# P2.net
KiCad netlist of a schematic drawn in EAGLE
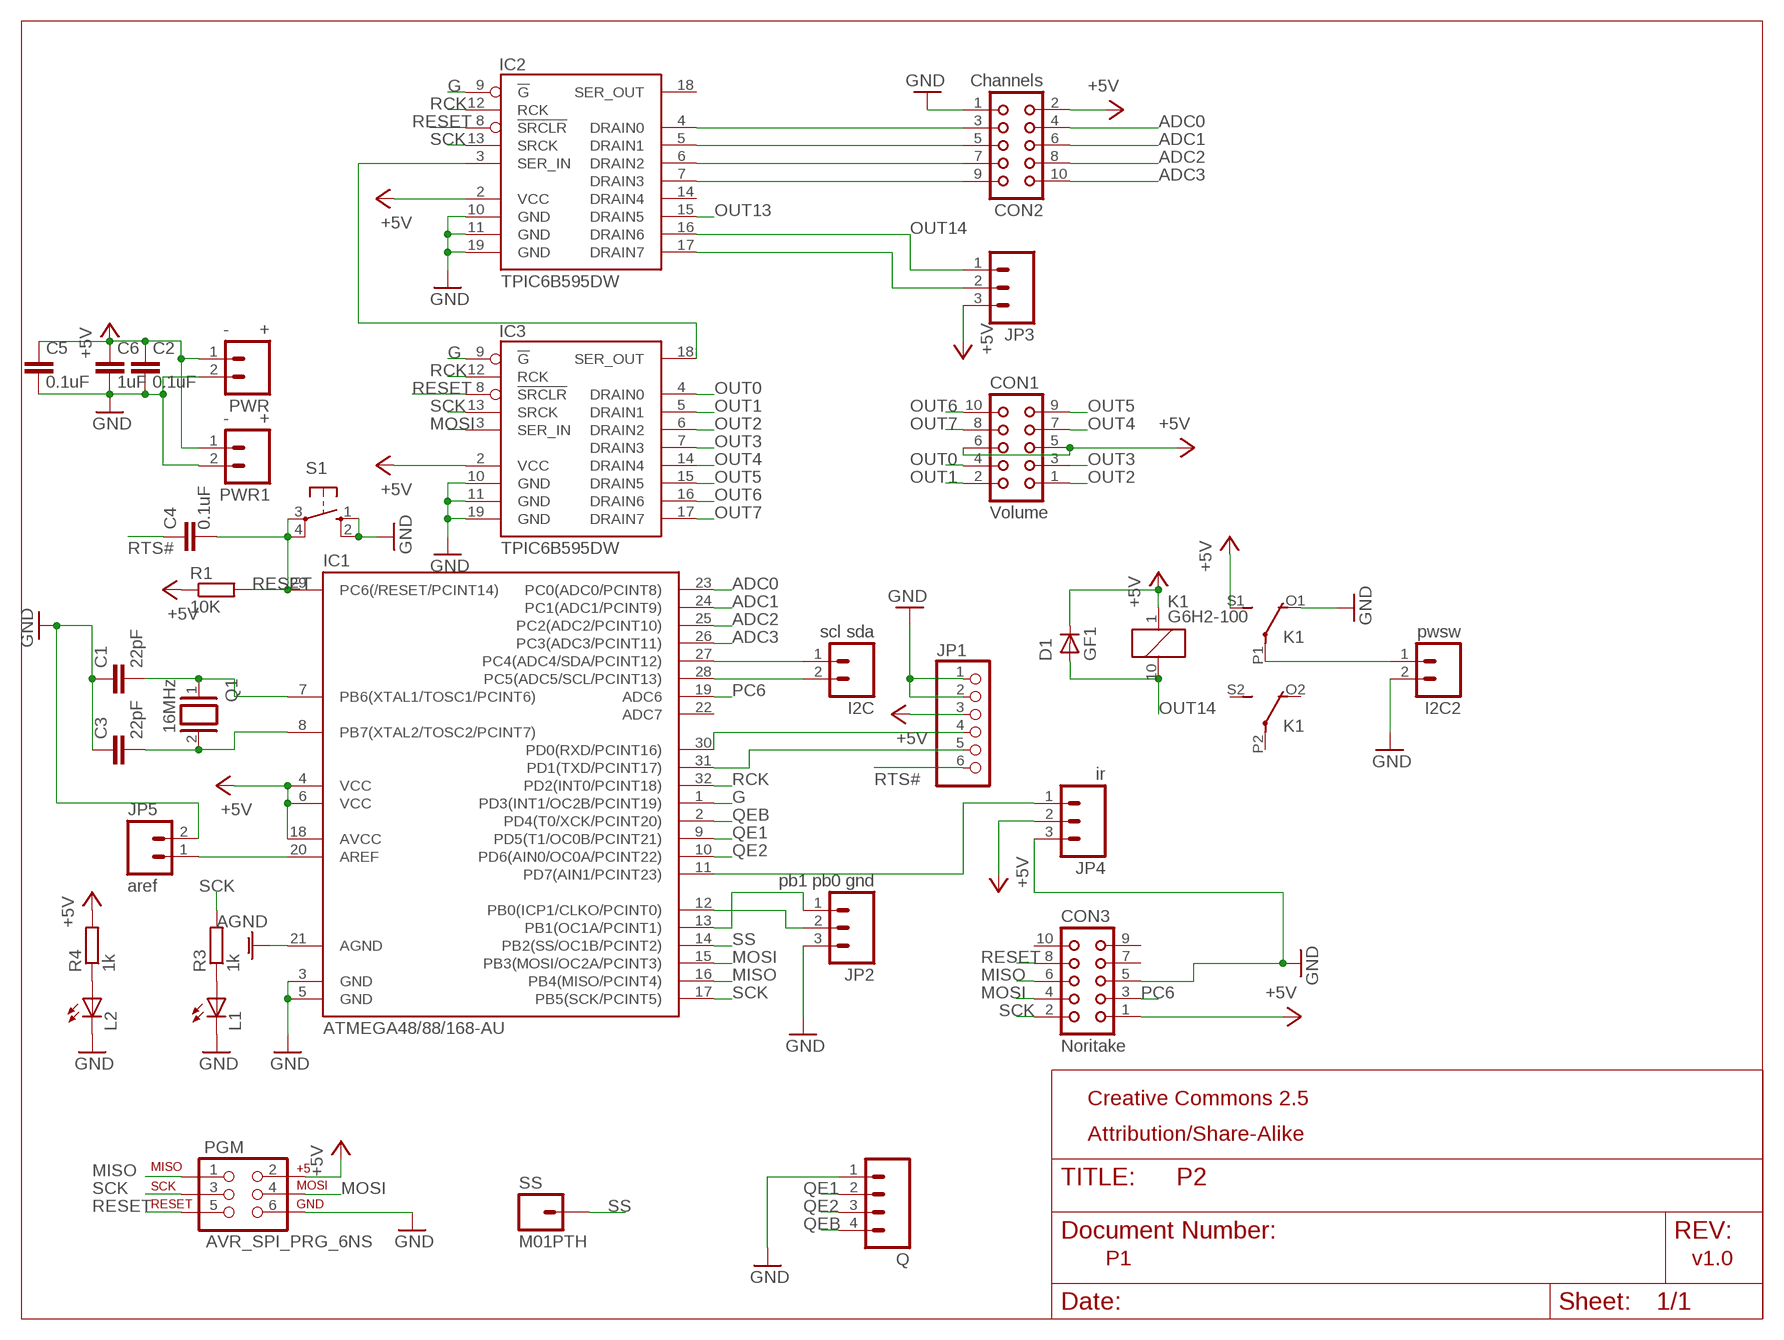
[diagram p0: schematic, sheet 1]

(export (version "E")
  (design (tool "Eeschema 10.0.6"))
  (components
    (comp (ref "C1")
      (value "22pF")
      (footprint "eagle-import:C0805")
      (libsource (lib "eagle-import") (part "C-EUC0805"))
    )
    (comp (ref "C2")
      (value "0.1uF")
      (footprint "eagle-import:C0805")
      (libsource (lib "eagle-import") (part "C-EUC0805"))
    )
    (comp (ref "C3")
      (value "22pF")
      (footprint "eagle-import:C0805")
      (libsource (lib "eagle-import") (part "C-EUC0805"))
    )
    (comp (ref "C4")
      (value "0.1uF")
      (footprint "eagle-import:C0805")
      (libsource (lib "eagle-import") (part "C-EUC0805"))
    )
    (comp (ref "C5")
      (value "0.1uF")
      (footprint "eagle-import:C0805")
      (libsource (lib "eagle-import") (part "C-EUC0805"))
    )
    (comp (ref "C6")
      (value "1uF")
      (footprint "eagle-import:C0805")
      (libsource (lib "eagle-import") (part "C-EUC0805"))
    )
    (comp (ref "CON1")
      (value "Volume")
      (footprint "eagle-import:CON10L")
      (libsource (lib "eagle-import") (part "CON10L"))
    )
    (comp (ref "CON2")
      (value "Channels")
      (footprint "eagle-import:CON10L")
      (libsource (lib "eagle-import") (part "CON10L"))
    )
    (comp (ref "CON3")
      (value "Noritake")
      (footprint "eagle-import:CON10L")
      (libsource (lib "eagle-import") (part "CON10L"))
    )
    (comp (ref "D1")
      (value "GF1")
      (footprint "eagle-import:SMA-DO214AC")
      (libsource (lib "eagle-import") (part "GF1"))
    )
    (comp (ref "I2C")
      (value "scl sda")
      (footprint "eagle-import:1X02")
      (libsource (lib "eagle-import") (part "M02PTH"))
    )
    (comp (ref "I2C2")
      (value "pwsw")
      (footprint "eagle-import:1X02")
      (libsource (lib "eagle-import") (part "M02PTH"))
    )
    (comp (ref "IC1")
      (value "ATMEGA48/88/168-AU")
      (footprint "eagle-import:TQFP32-08")
      (libsource (lib "eagle-import") (part "ATMEGA48/88/168-AU"))
    )
    (comp (ref "IC2")
      (value "TPIC6B595DW")
      (footprint "eagle-import:SO20W")
      (libsource (lib "eagle-import") (part "TPIC6B595DW"))
    )
    (comp (ref "IC3")
      (value "TPIC6B595DW")
      (footprint "eagle-import:SO20W")
      (libsource (lib "eagle-import") (part "TPIC6B595DW"))
    )
    (comp (ref "JP1")
      (value "PINHD-1X6CLEAN")
      (footprint "eagle-import:1X06-CLEAN")
      (libsource (lib "eagle-import") (part "PINHD-1X6CLEAN"))
    )
    (comp (ref "JP2")
      (value "pb1 pb0 gnd")
      (footprint "eagle-import:1X03")
      (libsource (lib "eagle-import") (part "M03PTH"))
    )
    (comp (ref "JP3")
      (value "M03PTH")
      (footprint "eagle-import:1X03")
      (libsource (lib "eagle-import") (part "M03PTH"))
    )
    (comp (ref "JP4")
      (value "ir")
      (footprint "eagle-import:1X03")
      (libsource (lib "eagle-import") (part "M03PTH"))
    )
    (comp (ref "JP5")
      (value "aref")
      (footprint "eagle-import:1X02")
      (libsource (lib "eagle-import") (part "M02PTH"))
    )
    (comp (ref "K1")
      (value "G6H2-100")
      (footprint "eagle-import:G6H2-100")
      (libsource (lib "eagle-import") (part "G6H2-100"))
    )
    (comp (ref "L1")
      (value "LEDSML0805")
      (footprint "eagle-import:SML0805")
      (libsource (lib "eagle-import") (part "LEDSML0805"))
    )
    (comp (ref "L2")
      (value "LEDSML0805")
      (footprint "eagle-import:SML0805")
      (libsource (lib "eagle-import") (part "LEDSML0805"))
    )
    (comp (ref "PGM")
      (value "AVR_SPI_PRG_6NS")
      (footprint "eagle-import:2X3-NS")
      (libsource (lib "eagle-import") (part "AVR_SPI_PRG_6NS"))
    )
    (comp (ref "PWR")
      (value "- +")
      (footprint "eagle-import:1X02")
      (libsource (lib "eagle-import") (part "M02PTH"))
    )
    (comp (ref "PWR1")
      (value "- +")
      (footprint "eagle-import:1X02")
      (libsource (lib "eagle-import") (part "M02PTH"))
    )
    (comp (ref "Q")
      (value "M04PTH")
      (footprint "eagle-import:1X04")
      (libsource (lib "eagle-import") (part "M04PTH"))
    )
    (comp (ref "Q1")
      (value "16MHz")
      (footprint "eagle-import:QS")
      (libsource (lib "eagle-import") (part "XTAL/S"))
    )
    (comp (ref "R1")
      (value "10K")
      (footprint "eagle-import:M0805")
      (libsource (lib "eagle-import") (part "R-EU_M0805"))
    )
    (comp (ref "R3")
      (value "1k")
      (footprint "eagle-import:M0805")
      (libsource (lib "eagle-import") (part "R-EU_M0805"))
    )
    (comp (ref "R4")
      (value "1k")
      (footprint "eagle-import:M0805")
      (libsource (lib "eagle-import") (part "R-EU_M0805"))
    )
    (comp (ref "S1")
      (value "10-XX")
      (footprint "eagle-import:B3F-10XX")
      (fields (field (name "MPN") "B3F-1000"))
      (libsource (lib "eagle-import") (part "10-XX"))
    )
    (comp (ref "SS")
      (value "M01PTH")
      (footprint "eagle-import:1X01")
      (libsource (lib "eagle-import") (part "M01PTH"))
    )
  )
  (nets
    (net (code "1") (name "+5V") (class "Default")
      (node (ref "C2") (pin "1") (pinfunction "1_1") (pintype "passive"))
      (node (ref "C5") (pin "1") (pinfunction "1_1") (pintype "passive"))
      (node (ref "C6") (pin "1") (pinfunction "1_1") (pintype "passive"))
      (node (ref "CON1") (pin "5") (pinfunction "5_5") (pintype "passive"))
      (node (ref "CON1") (pin "6") (pinfunction "6_6") (pintype "passive"))
      (node (ref "CON2") (pin "2") (pinfunction "2_2") (pintype "passive"))
      (node (ref "CON3") (pin "1") (pinfunction "1_1") (pintype "passive"))
      (node (ref "D1") (pin "K") (pinfunction "C_K") (pintype "passive"))
      (node (ref "IC1") (pin "18") (pinfunction "AVCC_18") (pintype "passive"))
      (node (ref "IC1") (pin "4") (pinfunction "VCC_4") (pintype "power_in"))
      (node (ref "IC1") (pin "6") (pinfunction "VCC_6") (pintype "power_in"))
      (node (ref "IC2") (pin "2") (pinfunction "VCC_2") (pintype "power_in"))
      (node (ref "IC3") (pin "2") (pinfunction "VCC_2") (pintype "power_in"))
      (node (ref "JP1") (pin "3") (pinfunction "3_3") (pintype "passive"))
      (node (ref "JP3") (pin "3") (pinfunction "3_3") (pintype "passive"))
      (node (ref "JP4") (pin "2") (pinfunction "2_2") (pintype "passive"))
      (node (ref "K1") (pin "1") (pinfunction "1_1") (pintype "passive"))
      (node (ref "K1") (pin "S1") (pinfunction "S_S1") (pintype "passive"))
      (node (ref "PGM") (pin "2") (pinfunction "2_2") (pintype "passive"))
      (node (ref "PWR") (pin "1") (pinfunction "1_1") (pintype "passive"))
      (node (ref "PWR1") (pin "1") (pinfunction "1_1") (pintype "passive"))
      (node (ref "R1") (pin "1") (pinfunction "1_1") (pintype "passive"))
      (node (ref "R4") (pin "2") (pinfunction "2_2") (pintype "passive"))
    )
    (net (code "2") (name "/ADC0") (class "Default")
      (node (ref "CON2") (pin "4") (pinfunction "4_4") (pintype "passive"))
      (node (ref "IC1") (pin "23") (pinfunction "PC0(ADC0/PCINT8)_23") (pintype "bidirectional"))
    )
    (net (code "3") (name "/ADC1") (class "Default")
      (node (ref "CON2") (pin "6") (pinfunction "6_6") (pintype "passive"))
      (node (ref "IC1") (pin "24") (pinfunction "PC1(ADC1/PCINT9)_24") (pintype "bidirectional"))
    )
    (net (code "4") (name "/ADC2") (class "Default")
      (node (ref "CON2") (pin "8") (pinfunction "8_8") (pintype "passive"))
      (node (ref "IC1") (pin "25") (pinfunction "PC2(ADC2/PCINT10)_25") (pintype "bidirectional"))
    )
    (net (code "5") (name "/ADC3") (class "Default")
      (node (ref "CON2") (pin "10") (pinfunction "10_10") (pintype "passive"))
      (node (ref "IC1") (pin "26") (pinfunction "PC3(ADC3/PCINT11)_26") (pintype "bidirectional"))
    )
    (net (code "6") (name "/G") (class "Default")
      (node (ref "IC1") (pin "1") (pinfunction "PD3(INT1/OC2B/PCINT19)_1") (pintype "bidirectional"))
      (node (ref "IC2") (pin "9") (pinfunction "~{G}_9") (pintype "input"))
      (node (ref "IC3") (pin "9") (pinfunction "~{G}_9") (pintype "input"))
    )
    (net (code "7") (name "/MISO") (class "Default")
      (node (ref "CON3") (pin "6") (pinfunction "6_6") (pintype "passive"))
      (node (ref "IC1") (pin "16") (pinfunction "PB4(MISO/PCINT4)_16") (pintype "bidirectional"))
      (node (ref "PGM") (pin "1") (pinfunction "1_1") (pintype "passive"))
    )
    (net (code "8") (name "/MOSI") (class "Default")
      (node (ref "CON3") (pin "4") (pinfunction "4_4") (pintype "passive"))
      (node (ref "IC1") (pin "15") (pinfunction "PB3(MOSI/OC2A/PCINT3)_15") (pintype "bidirectional"))
      (node (ref "IC3") (pin "3") (pinfunction "SER_IN_3") (pintype "input"))
      (node (ref "PGM") (pin "4") (pinfunction "4_4") (pintype "passive"))
    )
    (net (code "9") (name "/OUT0") (class "Default")
      (node (ref "CON1") (pin "4") (pinfunction "4_4") (pintype "passive"))
      (node (ref "IC3") (pin "4") (pinfunction "DRAIN0_4") (pintype "open_collector"))
    )
    (net (code "10") (name "/OUT1") (class "Default")
      (node (ref "CON1") (pin "2") (pinfunction "2_2") (pintype "passive"))
      (node (ref "IC3") (pin "5") (pinfunction "DRAIN1_5") (pintype "open_collector"))
    )
    (net (code "11") (name "/OUT2") (class "Default")
      (node (ref "CON1") (pin "1") (pinfunction "1_1") (pintype "passive"))
      (node (ref "IC3") (pin "6") (pinfunction "DRAIN2_6") (pintype "open_collector"))
    )
    (net (code "12") (name "/OUT3") (class "Default")
      (node (ref "CON1") (pin "3") (pinfunction "3_3") (pintype "passive"))
      (node (ref "IC3") (pin "7") (pinfunction "DRAIN3_7") (pintype "open_collector"))
    )
    (net (code "13") (name "/OUT4") (class "Default")
      (node (ref "CON1") (pin "7") (pinfunction "7_7") (pintype "passive"))
      (node (ref "IC3") (pin "14") (pinfunction "DRAIN4_14") (pintype "open_collector"))
    )
    (net (code "14") (name "/OUT5") (class "Default")
      (node (ref "CON1") (pin "9") (pinfunction "9_9") (pintype "passive"))
      (node (ref "IC3") (pin "15") (pinfunction "DRAIN5_15") (pintype "open_collector"))
    )
    (net (code "15") (name "/OUT6") (class "Default")
      (node (ref "CON1") (pin "10") (pinfunction "10_10") (pintype "passive"))
      (node (ref "IC3") (pin "16") (pinfunction "DRAIN6_16") (pintype "open_collector"))
    )
    (net (code "16") (name "/OUT7") (class "Default")
      (node (ref "CON1") (pin "8") (pinfunction "8_8") (pintype "passive"))
      (node (ref "IC3") (pin "17") (pinfunction "DRAIN7_17") (pintype "open_collector"))
    )
    (net (code "17") (name "/OUT13") (class "Default")
      (node (ref "IC2") (pin "15") (pinfunction "DRAIN5_15") (pintype "open_collector"))
    )
    (net (code "18") (name "/OUT14") (class "Default")
      (node (ref "D1") (pin "A") (pinfunction "A_A") (pintype "passive"))
      (node (ref "IC2") (pin "16") (pinfunction "DRAIN6_16") (pintype "open_collector"))
      (node (ref "JP3") (pin "1") (pinfunction "1_1") (pintype "passive"))
      (node (ref "K1") (pin "10") (pinfunction "2_10") (pintype "passive"))
    )
    (net (code "19") (name "/PC6") (class "Default")
      (node (ref "CON3") (pin "3") (pinfunction "3_3") (pintype "passive"))
      (node (ref "IC1") (pin "19") (pinfunction "ADC6_19") (pintype "passive"))
    )
    (net (code "20") (name "/QE1") (class "Default")
      (node (ref "IC1") (pin "9") (pinfunction "PD5(T1/OC0B/PCINT21)_9") (pintype "bidirectional"))
      (node (ref "Q") (pin "2") (pinfunction "2_2") (pintype "passive"))
    )
    (net (code "21") (name "/QE2") (class "Default")
      (node (ref "IC1") (pin "10") (pinfunction "PD6(AIN0/OC0A/PCINT22)_10") (pintype "bidirectional"))
      (node (ref "Q") (pin "3") (pinfunction "3_3") (pintype "passive"))
    )
    (net (code "22") (name "/QEB") (class "Default")
      (node (ref "IC1") (pin "2") (pinfunction "PD4(T0/XCK/PCINT20)_2") (pintype "bidirectional"))
      (node (ref "Q") (pin "4") (pinfunction "4_4") (pintype "passive"))
    )
    (net (code "23") (name "/RCK") (class "Default")
      (node (ref "IC1") (pin "32") (pinfunction "PD2(INT0/PCINT18)_32") (pintype "bidirectional"))
      (node (ref "IC2") (pin "12") (pinfunction "RCK_12") (pintype "input"))
      (node (ref "IC3") (pin "12") (pinfunction "RCK_12") (pintype "input"))
    )
    (net (code "24") (name "/RESET") (class "Default")
      (node (ref "C4") (pin "2") (pinfunction "2_2") (pintype "passive"))
      (node (ref "CON3") (pin "8") (pinfunction "8_8") (pintype "passive"))
      (node (ref "IC1") (pin "29") (pinfunction "PC6(/RESET/PCINT14)_29") (pintype "bidirectional"))
      (node (ref "IC2") (pin "8") (pinfunction "~{SRCLR}_8") (pintype "input"))
      (node (ref "IC3") (pin "8") (pinfunction "~{SRCLR}_8") (pintype "input"))
      (node (ref "PGM") (pin "5") (pinfunction "5_5") (pintype "passive"))
      (node (ref "R1") (pin "2") (pinfunction "2_2") (pintype "passive"))
      (node (ref "S1") (pin "3") (pinfunction "P_3") (pintype "passive"))
      (node (ref "S1") (pin "4") (pinfunction "P1_4") (pintype "passive"))
    )
    (net (code "25") (name "/RTS#") (class "Default")
      (node (ref "C4") (pin "1") (pinfunction "1_1") (pintype "passive"))
      (node (ref "JP1") (pin "6") (pinfunction "6_6") (pintype "passive"))
    )
    (net (code "26") (name "/SCK") (class "Default")
      (node (ref "CON3") (pin "2") (pinfunction "2_2") (pintype "passive"))
      (node (ref "IC1") (pin "17") (pinfunction "PB5(SCK/PCINT5)_17") (pintype "bidirectional"))
      (node (ref "IC2") (pin "13") (pinfunction "SRCK_13") (pintype "input"))
      (node (ref "IC3") (pin "13") (pinfunction "SRCK_13") (pintype "input"))
      (node (ref "PGM") (pin "3") (pinfunction "3_3") (pintype "passive"))
      (node (ref "R3") (pin "2") (pinfunction "2_2") (pintype "passive"))
    )
    (net (code "27") (name "/SS") (class "Default")
      (node (ref "IC1") (pin "14") (pinfunction "PB2(SS/OC1B/PCINT2)_14") (pintype "bidirectional"))
      (node (ref "SS") (pin "1") (pinfunction "1_1") (pintype "passive"))
    )
    (net (code "28") (name "AGND") (class "Default")
      (node (ref "IC1") (pin "21") (pinfunction "AGND_21") (pintype "power_in"))
    )
    (net (code "29") (name "GND") (class "Default")
      (node (ref "C1") (pin "1") (pinfunction "1_1") (pintype "passive"))
      (node (ref "C2") (pin "2") (pinfunction "2_2") (pintype "passive"))
      (node (ref "C3") (pin "1") (pinfunction "1_1") (pintype "passive"))
      (node (ref "C5") (pin "2") (pinfunction "2_2") (pintype "passive"))
      (node (ref "C6") (pin "2") (pinfunction "2_2") (pintype "passive"))
      (node (ref "CON2") (pin "1") (pinfunction "1_1") (pintype "passive"))
      (node (ref "CON3") (pin "5") (pinfunction "5_5") (pintype "passive"))
      (node (ref "I2C2") (pin "2") (pinfunction "2_2") (pintype "passive"))
      (node (ref "IC1") (pin "3") (pinfunction "GND_3") (pintype "power_in"))
      (node (ref "IC1") (pin "5") (pinfunction "GND_5") (pintype "power_in"))
      (node (ref "IC2") (pin "10") (pinfunction "GND_10") (pintype "power_in"))
      (node (ref "IC2") (pin "11") (pinfunction "GND_11") (pintype "power_in"))
      (node (ref "IC2") (pin "19") (pinfunction "GND_19") (pintype "power_in"))
      (node (ref "IC3") (pin "10") (pinfunction "GND_10") (pintype "power_in"))
      (node (ref "IC3") (pin "11") (pinfunction "GND_11") (pintype "power_in"))
      (node (ref "IC3") (pin "19") (pinfunction "GND_19") (pintype "power_in"))
      (node (ref "JP1") (pin "1") (pinfunction "1_1") (pintype "passive"))
      (node (ref "JP1") (pin "2") (pinfunction "2_2") (pintype "passive"))
      (node (ref "JP2") (pin "3") (pinfunction "3_3") (pintype "passive"))
      (node (ref "JP4") (pin "3") (pinfunction "3_3") (pintype "passive"))
      (node (ref "JP5") (pin "2") (pinfunction "2_2") (pintype "passive"))
      (node (ref "K1") (pin "O1") (pinfunction "O_O1") (pintype "passive"))
      (node (ref "L1") (pin "C") (pinfunction "C_C") (pintype "passive"))
      (node (ref "L2") (pin "C") (pinfunction "C_C") (pintype "passive"))
      (node (ref "PGM") (pin "6") (pinfunction "6_6") (pintype "passive"))
      (node (ref "PWR") (pin "2") (pinfunction "2_2") (pintype "passive"))
      (node (ref "PWR1") (pin "2") (pinfunction "2_2") (pintype "passive"))
      (node (ref "Q") (pin "1") (pinfunction "1_1") (pintype "passive"))
      (node (ref "S1") (pin "1") (pinfunction "S_1") (pintype "passive"))
      (node (ref "S1") (pin "2") (pinfunction "S1_2") (pintype "passive"))
    )
    (net (code "30") (name "Net-(IC1-AREF)") (class "Default")
      (node (ref "IC1") (pin "20") (pinfunction "AREF_20") (pintype "passive"))
      (node (ref "JP5") (pin "1") (pinfunction "1_1") (pintype "passive"))
    )
    (net (code "31") (name "Net-(IC1-PB0(ICP1{slash}CLKO{slash}PCINT0))") (class "Default")
      (node (ref "IC1") (pin "12") (pinfunction "PB0(ICP1/CLKO/PCINT0)_12") (pintype "bidirectional"))
      (node (ref "JP2") (pin "2") (pinfunction "2_2") (pintype "passive"))
    )
    (net (code "32") (name "Net-(IC1-PB1(OC1A{slash}PCINT1))") (class "Default")
      (node (ref "IC1") (pin "13") (pinfunction "PB1(OC1A/PCINT1)_13") (pintype "bidirectional"))
      (node (ref "JP2") (pin "1") (pinfunction "1_1") (pintype "passive"))
    )
    (net (code "33") (name "Net-(IC1-PB6(XTAL1{slash}TOSC1{slash}PCINT6))") (class "Default")
      (node (ref "C1") (pin "2") (pinfunction "2_2") (pintype "passive"))
      (node (ref "IC1") (pin "7") (pinfunction "PB6(XTAL1/TOSC1/PCINT6)_7") (pintype "bidirectional"))
      (node (ref "Q1") (pin "1") (pinfunction "1_1") (pintype "passive"))
    )
    (net (code "34") (name "Net-(IC1-PB7(XTAL2{slash}TOSC2{slash}PCINT7))") (class "Default")
      (node (ref "C3") (pin "2") (pinfunction "2_2") (pintype "passive"))
      (node (ref "IC1") (pin "8") (pinfunction "PB7(XTAL2/TOSC2/PCINT7)_8") (pintype "bidirectional"))
      (node (ref "Q1") (pin "2") (pinfunction "2_2") (pintype "passive"))
    )
    (net (code "35") (name "Net-(IC1-PC4(ADC4{slash}SDA{slash}PCINT12))") (class "Default")
      (node (ref "I2C") (pin "1") (pinfunction "1_1") (pintype "passive"))
      (node (ref "IC1") (pin "27") (pinfunction "PC4(ADC4/SDA/PCINT12)_27") (pintype "bidirectional"))
    )
    (net (code "36") (name "Net-(IC1-PC5(ADC5{slash}SCL{slash}PCINT13))") (class "Default")
      (node (ref "I2C") (pin "2") (pinfunction "2_2") (pintype "passive"))
      (node (ref "IC1") (pin "28") (pinfunction "PC5(ADC5/SCL/PCINT13)_28") (pintype "bidirectional"))
    )
    (net (code "37") (name "Net-(IC1-PD0(RXD{slash}PCINT16))") (class "Default")
      (node (ref "IC1") (pin "30") (pinfunction "PD0(RXD/PCINT16)_30") (pintype "bidirectional"))
      (node (ref "JP1") (pin "4") (pinfunction "4_4") (pintype "passive"))
    )
    (net (code "38") (name "Net-(IC1-PD1(TXD{slash}PCINT17))") (class "Default")
      (node (ref "IC1") (pin "31") (pinfunction "PD1(TXD/PCINT17)_31") (pintype "bidirectional"))
      (node (ref "JP1") (pin "5") (pinfunction "5_5") (pintype "passive"))
    )
    (net (code "39") (name "Net-(IC1-PD7(AIN1{slash}PCINT23))") (class "Default")
      (node (ref "IC1") (pin "11") (pinfunction "PD7(AIN1/PCINT23)_11") (pintype "bidirectional"))
      (node (ref "JP4") (pin "1") (pinfunction "1_1") (pintype "passive"))
    )
    (net (code "40") (name "Net-(IC2-DRAIN0)") (class "Default")
      (node (ref "CON2") (pin "3") (pinfunction "3_3") (pintype "passive"))
      (node (ref "IC2") (pin "4") (pinfunction "DRAIN0_4") (pintype "open_collector"))
    )
    (net (code "41") (name "Net-(IC2-DRAIN1)") (class "Default")
      (node (ref "CON2") (pin "5") (pinfunction "5_5") (pintype "passive"))
      (node (ref "IC2") (pin "5") (pinfunction "DRAIN1_5") (pintype "open_collector"))
    )
    (net (code "42") (name "Net-(IC2-DRAIN2)") (class "Default")
      (node (ref "CON2") (pin "7") (pinfunction "7_7") (pintype "passive"))
      (node (ref "IC2") (pin "6") (pinfunction "DRAIN2_6") (pintype "open_collector"))
    )
    (net (code "43") (name "Net-(IC2-DRAIN3)") (class "Default")
      (node (ref "CON2") (pin "9") (pinfunction "9_9") (pintype "passive"))
      (node (ref "IC2") (pin "7") (pinfunction "DRAIN3_7") (pintype "open_collector"))
    )
    (net (code "44") (name "Net-(IC2-DRAIN7)") (class "Default")
      (node (ref "IC2") (pin "17") (pinfunction "DRAIN7_17") (pintype "open_collector"))
      (node (ref "JP3") (pin "2") (pinfunction "2_2") (pintype "passive"))
    )
    (net (code "45") (name "Net-(IC2-SER_IN)") (class "Default")
      (node (ref "IC2") (pin "3") (pinfunction "SER_IN_3") (pintype "input"))
      (node (ref "IC3") (pin "18") (pinfunction "SER_OUT_18") (pintype "output"))
    )
    (net (code "46") (name "Net-(K1B-P)") (class "Default")
      (node (ref "I2C2") (pin "1") (pinfunction "1_1") (pintype "passive"))
      (node (ref "K1") (pin "P1") (pinfunction "P_P1") (pintype "passive"))
    )
    (net (code "47") (name "Net-(L1-PadA)") (class "Default")
      (node (ref "L1") (pin "A") (pinfunction "A_A") (pintype "passive"))
      (node (ref "R3") (pin "1") (pinfunction "1_1") (pintype "passive"))
    )
    (net (code "48") (name "Net-(L2-PadA)") (class "Default")
      (node (ref "L2") (pin "A") (pinfunction "A_A") (pintype "passive"))
      (node (ref "R4") (pin "1") (pinfunction "1_1") (pintype "passive"))
    )
    (net (code "49") (name "unconnected-(CON3-Pad7)") (class "Default")
      (node (ref "CON3") (pin "7") (pinfunction "7_7") (pintype "passive"))
    )
    (net (code "50") (name "unconnected-(CON3-Pad9)") (class "Default")
      (node (ref "CON3") (pin "9") (pinfunction "9_9") (pintype "passive"))
    )
    (net (code "51") (name "unconnected-(CON3-Pad10)") (class "Default")
      (node (ref "CON3") (pin "10") (pinfunction "10_10") (pintype "passive"))
    )
    (net (code "52") (name "unconnected-(IC1-ADC7-Pad22)") (class "Default")
      (node (ref "IC1") (pin "22") (pinfunction "ADC7_22") (pintype "passive"))
    )
    (net (code "53") (name "unconnected-(IC2-DRAIN4-Pad14)") (class "Default")
      (node (ref "IC2") (pin "14") (pinfunction "DRAIN4_14") (pintype "open_collector"))
    )
    (net (code "54") (name "unconnected-(IC2-SER_OUT-Pad18)") (class "Default")
      (node (ref "IC2") (pin "18") (pinfunction "SER_OUT_18") (pintype "output"))
    )
    (net (code "55") (name "unconnected-(K1C-O-PadO2)") (class "Default")
      (node (ref "K1") (pin "O2") (pinfunction "O_O2") (pintype "passive"))
    )
    (net (code "56") (name "unconnected-(K1C-P-PadP2)") (class "Default")
      (node (ref "K1") (pin "P2") (pinfunction "P_P2") (pintype "passive"))
    )
    (net (code "57") (name "unconnected-(K1C-S-PadS2)") (class "Default")
      (node (ref "K1") (pin "S2") (pinfunction "S_S2") (pintype "passive"))
    )
  )
)
